# light_digital_sensor.net
KiCad netlist of a schematic drawn in EAGLE
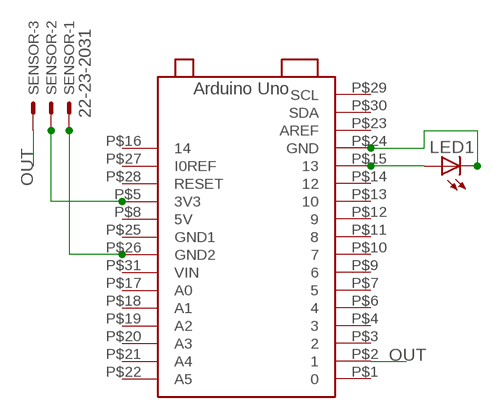
[diagram p0: schematic, sheet 1]

(export (version "E")
  (design (tool "Eeschema 10.0.6"))
  (components
    (comp (ref "LED1")
      (value "LED3MM")
      (footprint "eagle-import:LED3MM")
      (libsource (lib "eagle-import") (part "LED3MM"))
    )
    (comp (ref "SENSOR")
      (value "22-23-2031")
      (footprint "eagle-import:22-23-2031")
      (fields (field (name "MF") "MOLEX"))
      (libsource (lib "eagle-import") (part "22-23-2031"))
    )
    (comp (ref "U$1")
      (value "ARD_UNO")
      (footprint "eagle-import:ARD_UNO")
      (libsource (lib "eagle-import") (part "ARD_UNO"))
    )
  )
  (nets
    (net (code "1") (name "/OUT") (class "Default")
      (node (ref "SENSOR") (pin "3") (pinfunction "S_3") (pintype "passive"))
      (node (ref "U$1") (pin "P$2") (pinfunction "1_P$2") (pintype "bidirectional"))
    )
    (net (code "2") (name "Net-(LED1-C)") (class "Default")
      (node (ref "LED1") (pin "K") (pinfunction "C_K") (pintype "passive"))
      (node (ref "U$1") (pin "P$24") (pinfunction "GND_P$24") (pintype "bidirectional"))
    )
    (net (code "3") (name "Net-(SENSORA-S)") (class "Default")
      (node (ref "SENSOR") (pin "1") (pinfunction "S_1") (pintype "passive"))
      (node (ref "U$1") (pin "P$26") (pinfunction "GND2_P$26") (pintype "bidirectional"))
    )
    (net (code "4") (name "Net-(SENSORB-S)") (class "Default")
      (node (ref "SENSOR") (pin "2") (pinfunction "S_2") (pintype "passive"))
      (node (ref "U$1") (pin "P$5") (pinfunction "3V3_P$5") (pintype "bidirectional"))
    )
    (net (code "5") (name "Net-(U$1-13)") (class "Default")
      (node (ref "LED1") (pin "A") (pinfunction "A_A") (pintype "passive"))
      (node (ref "U$1") (pin "P$15") (pinfunction "13_P$15") (pintype "bidirectional"))
    )
    (net (code "6") (name "unconnected-(U$1-0-PadP$1)") (class "Default")
      (node (ref "U$1") (pin "P$1") (pinfunction "0_P$1") (pintype "bidirectional"))
    )
    (net (code "7") (name "unconnected-(U$1-2-PadP$3)") (class "Default")
      (node (ref "U$1") (pin "P$3") (pinfunction "2_P$3") (pintype "bidirectional"))
    )
    (net (code "8") (name "unconnected-(U$1-3-PadP$4)") (class "Default")
      (node (ref "U$1") (pin "P$4") (pinfunction "3_P$4") (pintype "bidirectional"))
    )
    (net (code "9") (name "unconnected-(U$1-4-PadP$6)") (class "Default")
      (node (ref "U$1") (pin "P$6") (pinfunction "4_P$6") (pintype "bidirectional"))
    )
    (net (code "10") (name "unconnected-(U$1-5-PadP$7)") (class "Default")
      (node (ref "U$1") (pin "P$7") (pinfunction "5_P$7") (pintype "bidirectional"))
    )
    (net (code "11") (name "unconnected-(U$1-5V-PadP$8)") (class "Default")
      (node (ref "U$1") (pin "P$8") (pinfunction "5V_P$8") (pintype "bidirectional"))
    )
    (net (code "12") (name "unconnected-(U$1-6-PadP$9)") (class "Default")
      (node (ref "U$1") (pin "P$9") (pinfunction "6_P$9") (pintype "bidirectional"))
    )
    (net (code "13") (name "unconnected-(U$1-7-PadP$10)") (class "Default")
      (node (ref "U$1") (pin "P$10") (pinfunction "7_P$10") (pintype "bidirectional"))
    )
    (net (code "14") (name "unconnected-(U$1-8-PadP$11)") (class "Default")
      (node (ref "U$1") (pin "P$11") (pinfunction "8_P$11") (pintype "bidirectional"))
    )
    (net (code "15") (name "unconnected-(U$1-9-PadP$12)") (class "Default")
      (node (ref "U$1") (pin "P$12") (pinfunction "9_P$12") (pintype "bidirectional"))
    )
    (net (code "16") (name "unconnected-(U$1-10-PadP$13)") (class "Default")
      (node (ref "U$1") (pin "P$13") (pinfunction "10_P$13") (pintype "bidirectional"))
    )
    (net (code "17") (name "unconnected-(U$1-12-PadP$14)") (class "Default")
      (node (ref "U$1") (pin "P$14") (pinfunction "12_P$14") (pintype "bidirectional"))
    )
    (net (code "18") (name "unconnected-(U$1-14-PadP$16)") (class "Default")
      (node (ref "U$1") (pin "P$16") (pinfunction "14_P$16") (pintype "bidirectional"))
    )
    (net (code "19") (name "unconnected-(U$1-A0-PadP$17)") (class "Default")
      (node (ref "U$1") (pin "P$17") (pinfunction "A0_P$17") (pintype "bidirectional"))
    )
    (net (code "20") (name "unconnected-(U$1-A1-PadP$18)") (class "Default")
      (node (ref "U$1") (pin "P$18") (pinfunction "A1_P$18") (pintype "bidirectional"))
    )
    (net (code "21") (name "unconnected-(U$1-A2-PadP$19)") (class "Default")
      (node (ref "U$1") (pin "P$19") (pinfunction "A2_P$19") (pintype "bidirectional"))
    )
    (net (code "22") (name "unconnected-(U$1-A3-PadP$20)") (class "Default")
      (node (ref "U$1") (pin "P$20") (pinfunction "A3_P$20") (pintype "bidirectional"))
    )
    (net (code "23") (name "unconnected-(U$1-A4-PadP$21)") (class "Default")
      (node (ref "U$1") (pin "P$21") (pinfunction "A4_P$21") (pintype "bidirectional"))
    )
    (net (code "24") (name "unconnected-(U$1-A5-PadP$22)") (class "Default")
      (node (ref "U$1") (pin "P$22") (pinfunction "A5_P$22") (pintype "bidirectional"))
    )
    (net (code "25") (name "unconnected-(U$1-AREF-PadP$23)") (class "Default")
      (node (ref "U$1") (pin "P$23") (pinfunction "AREF_P$23") (pintype "bidirectional"))
    )
    (net (code "26") (name "unconnected-(U$1-GND1-PadP$25)") (class "Default")
      (node (ref "U$1") (pin "P$25") (pinfunction "GND1_P$25") (pintype "bidirectional"))
    )
    (net (code "27") (name "unconnected-(U$1-I0REF-PadP$27)") (class "Default")
      (node (ref "U$1") (pin "P$27") (pinfunction "I0REF_P$27") (pintype "bidirectional"))
    )
    (net (code "28") (name "unconnected-(U$1-RESET-PadP$28)") (class "Default")
      (node (ref "U$1") (pin "P$28") (pinfunction "RESET_P$28") (pintype "bidirectional"))
    )
    (net (code "29") (name "unconnected-(U$1-SCL-PadP$29)") (class "Default")
      (node (ref "U$1") (pin "P$29") (pinfunction "SCL_P$29") (pintype "bidirectional"))
    )
    (net (code "30") (name "unconnected-(U$1-SDA-PadP$30)") (class "Default")
      (node (ref "U$1") (pin "P$30") (pinfunction "SDA_P$30") (pintype "bidirectional"))
    )
    (net (code "31") (name "unconnected-(U$1-VIN-PadP$31)") (class "Default")
      (node (ref "U$1") (pin "P$31") (pinfunction "VIN_P$31") (pintype "bidirectional"))
    )
  )
)
